# mach_nguyen_li_dttt1.net
KiCad netlist of a schematic drawn in Altium Designer
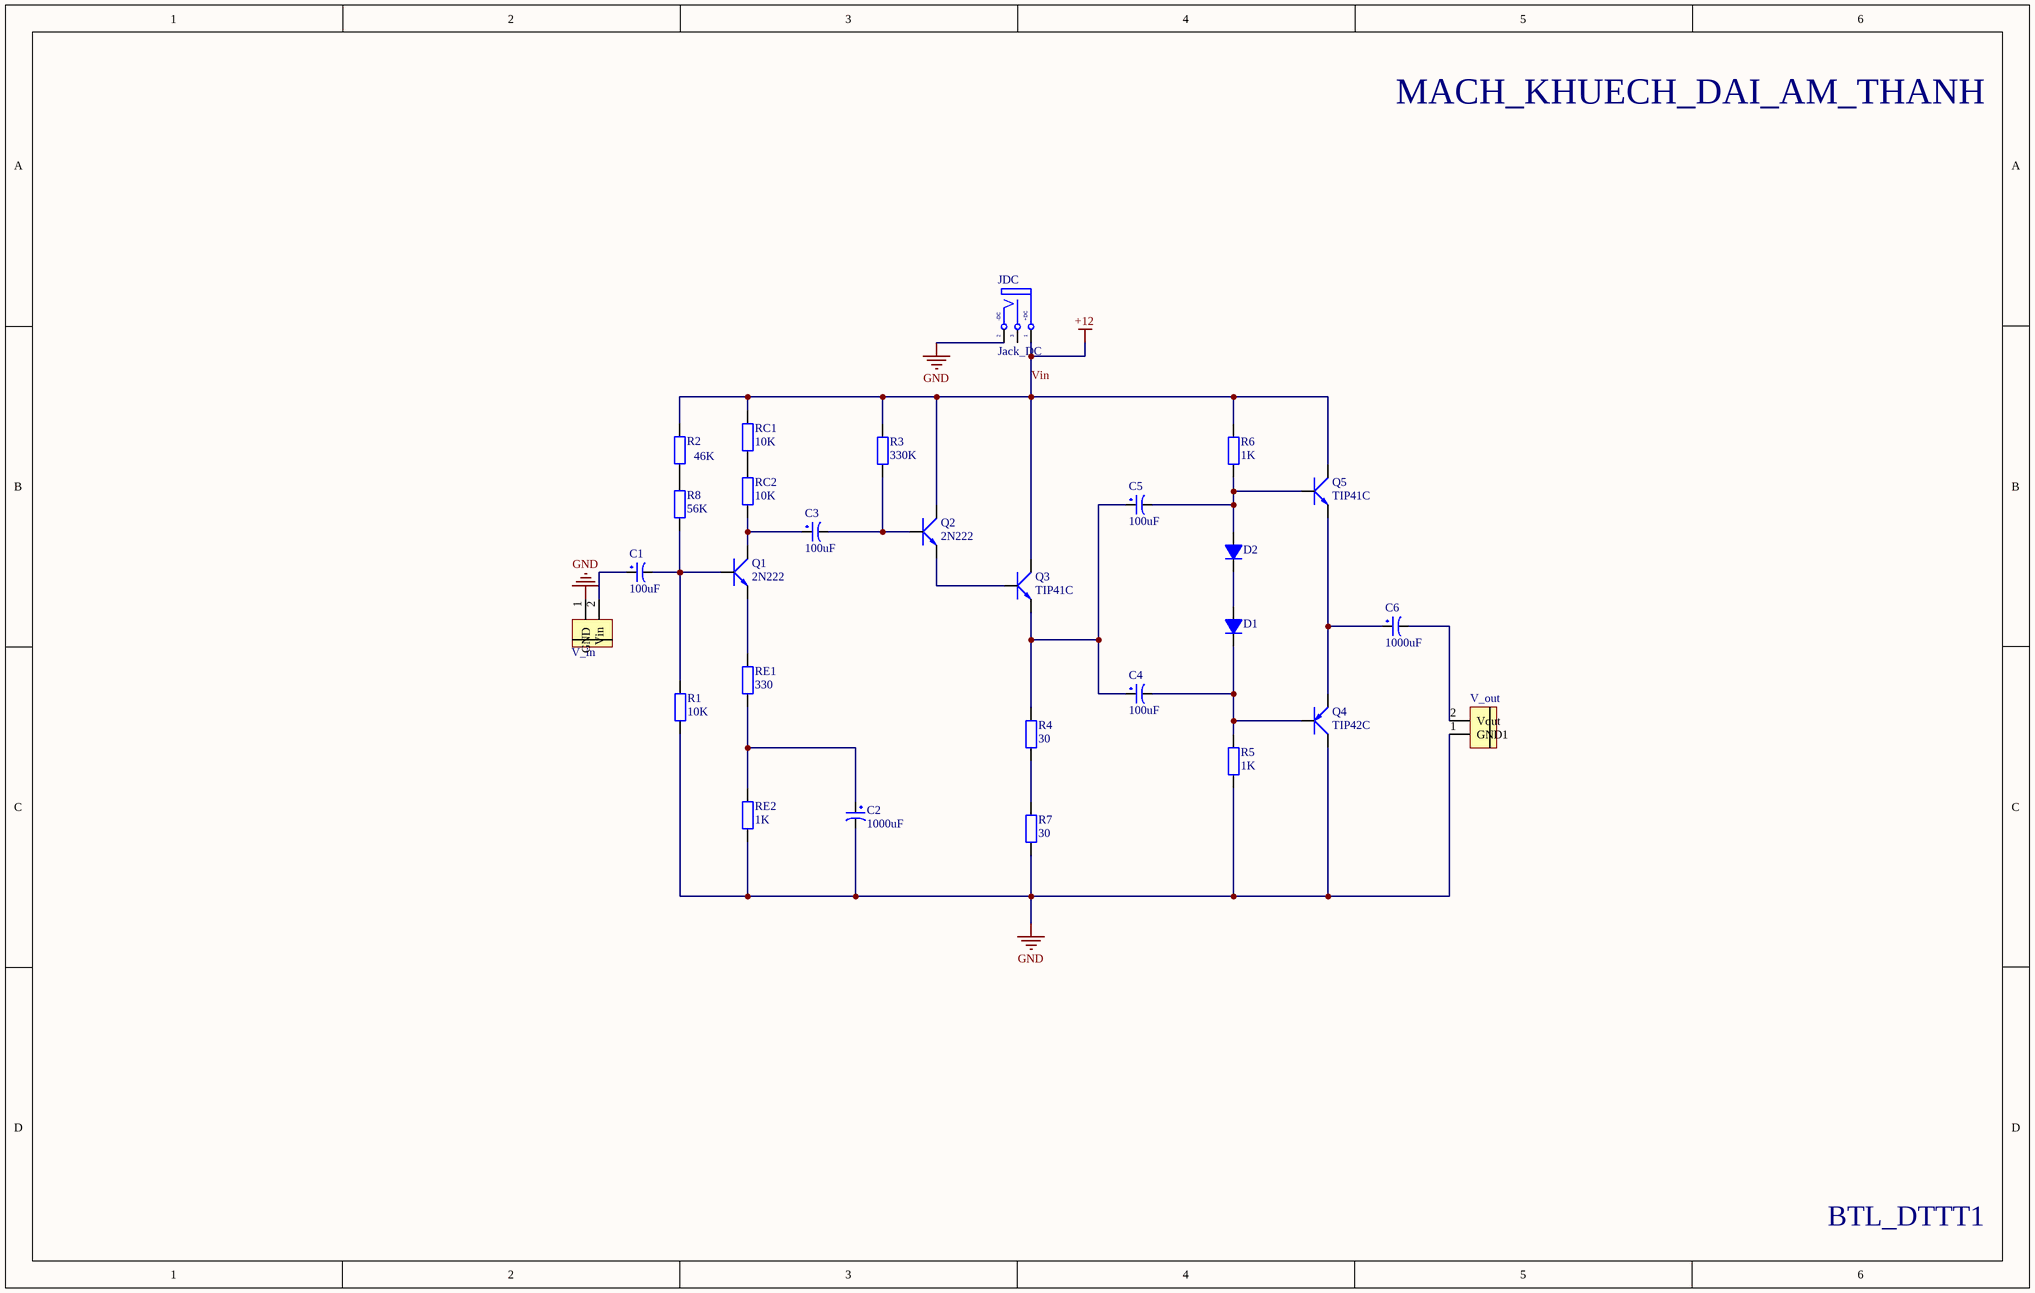
[diagram p0: mach_nguyen_li_dttt1.SchDoc]

(export (version "E")
  (design (tool "Eeschema 10.0.6"))
  (components
    (comp (ref "C1")
      (value "100uF")
      (footprint "tu hoa 5mm")
      (description "Cắm")
      (libsource (lib "Tu dien") (part "Tu Hoa 100uF 16V 5x11"))
    )
    (comp (ref "C2")
      (value "1000uF")
      (footprint "tu hoa 13mm")
      (description "Cắm")
      (libsource (lib "") (part "Tu Hoa 1000uF 25V 13x21_1"))
    )
    (comp (ref "C3")
      (value "100uF")
      (footprint "tu hoa 5mm")
      (description "Cắm")
      (libsource (lib "Tu dien") (part "Tu Hoa 100uF 16V 5x11"))
    )
    (comp (ref "C4")
      (value "100uF")
      (footprint "tu hoa 5mm")
      (description "Cắm")
      (libsource (lib "Tu dien") (part "Tu Hoa 100uF 16V 5x11"))
    )
    (comp (ref "C5")
      (value "100uF")
      (footprint "tu hoa 5mm")
      (description "Cắm")
      (libsource (lib "Tu dien") (part "Tu Hoa 100uF 16V 5x11"))
    )
    (comp (ref "C6")
      (value "1000uF")
      (footprint "tu hoa 13mm")
      (description "Cắm")
      (libsource (lib "Tu dien") (part "Tu Hoa 1000uF 25V 13x21"))
    )
    (comp (ref "D1")
      (value "100v")
      (footprint "DIODE 1A")
      (description "Cắm")
      (libsource (lib "Diode") (part "Diode 1N4007"))
    )
    (comp (ref "D2")
      (value "100v")
      (footprint "DIODE 1A")
      (description "Cắm")
      (libsource (lib "Diode") (part "Diode 1N4007"))
    )
    (comp (ref "JDC")
      (value "Jack_DC")
      (footprint "DC-IN_DC050-T")
      (description "Surface Mount，Right Angle DC Power Receptacle 2mm 6.4mm 4A 16V SMD AC/DC Power Connectors ROHS")
      (fields (field (name "PARTNUMBER") "DC050-T") (field (name "CREATOR") "Manhpd"))
      (libsource (lib "MKP_lib") (part "DCIN"))
    )
    (comp (ref "Q1")
      (value "2N222")
      (footprint "TO92-123")
      (description "NPN 600mW, ECB")
      (libsource (lib "Library") (part "2N222"))
    )
    (comp (ref "Q2")
      (value "2N222")
      (footprint "TO92-123")
      (description "NPN 600mW, ECB")
      (libsource (lib "Library") (part "2N222"))
    )
    (comp (ref "Q3")
      (value "TIP41C")
      (footprint "TO220-123")
      (description "NPN 2W, BCE")
      (libsource (lib "Library") (part "TIP41C"))
    )
    (comp (ref "Q4")
      (value "TIP42C")
      (footprint "TO220-123")
      (description "PNP 2W, BCE")
      (libsource (lib "Library") (part "TIP42C"))
    )
    (comp (ref "Q5")
      (value "TIP41C")
      (footprint "TO220-123")
      (description "NPN 2W, BCE")
      (libsource (lib "Library") (part "TIP41C"))
    )
    (comp (ref "R1")
      (value "10K")
      (footprint "tro vach 1/2w")
      (description "Cắm")
      (libsource (lib "Dien Tro") (part "Tro Vach 1/2W 5% 820R"))
    )
    (comp (ref "R2")
      (value "46K")
      (footprint "tro vach 1/2w")
      (description "Cắm")
      (libsource (lib "Dien Tro") (part "Tro Vach 1/2W 5% 820R"))
    )
    (comp (ref "R3")
      (value "330K")
      (footprint "tro vach 1/2w")
      (description "Cắm")
      (libsource (lib "Dien Tro") (part "Tro Vach 1/2W 5% 820R"))
    )
    (comp (ref "R4")
      (value "30")
      (footprint "tro vach 1/2w")
      (description "Cắm")
      (libsource (lib "Dien Tro") (part "Tro Vach 1/2W 5% 820R"))
    )
    (comp (ref "R5")
      (value "1K")
      (footprint "tro vach 1/2w")
      (description "Cắm")
      (libsource (lib "Dien Tro") (part "Tro Vach 1/2W 5% 820R"))
    )
    (comp (ref "R6")
      (value "1K")
      (footprint "tro vach 1/2w")
      (description "Cắm")
      (libsource (lib "Dien Tro") (part "Tro Vach 1/2W 5% 820R"))
    )
    (comp (ref "R7")
      (value "30")
      (footprint "tro vach 1/2w")
      (description "Cắm")
      (libsource (lib "Dien Tro") (part "Tro Vach 1/2W 5% 820R"))
    )
    (comp (ref "R8")
      (value "56K")
      (footprint "tro vach 1/2w")
      (description "Cắm")
      (libsource (lib "Dien Tro") (part "Tro Vach 1/2W 5% 820R"))
    )
    (comp (ref "RC1")
      (value "10K")
      (footprint "tro vach 1/2w")
      (description "Cắm")
      (libsource (lib "Dien Tro") (part "Tro Vach 1/2W 5% 820R"))
    )
    (comp (ref "RC2")
      (value "10K")
      (footprint "tro vach 1/2w")
      (description "Cắm")
      (libsource (lib "Dien Tro") (part "Tro Vach 1/2W 5% 820R"))
    )
    (comp (ref "RE1")
      (value "330")
      (footprint "tro vach 1/2w")
      (description "Cắm")
      (libsource (lib "Dien Tro") (part "Tro Vach 1/2W 5% 820R"))
    )
    (comp (ref "RE2")
      (value "1K")
      (footprint "tro vach 1/2w")
      (description "Cắm")
      (libsource (lib "Dien Tro") (part "Tro Vach 1/2W 5% 820R"))
    )
    (comp (ref "V_in")
      (value "CON 2 KF301")
      (footprint "Con 2 KF301 5.08")
      (description "Cắm")
      (libsource (lib "") (part "CON 2 KF301_1"))
    )
    (comp (ref "V_out")
      (value "CON 2 KF301")
      (footprint "Con 2 KF301 5.08")
      (description "Cắm")
      (libsource (lib "Connector") (part "CON 2 KF301"))
    )
  )
  (nets
    (net (code "1") (name "+12") (class "Default")
      (node (ref "JDC") (pin "1") (pinfunction "T_1") (pintype "passive"))
      (node (ref "Q2") (pin "3") (pinfunction "C_3") (pintype "passive"))
      (node (ref "Q3") (pin "2") (pinfunction "C_2") (pintype "passive"))
      (node (ref "Q5") (pin "2") (pinfunction "C_2") (pintype "passive"))
      (node (ref "R2") (pin "2") (pinfunction "2_2") (pintype "passive"))
      (node (ref "R3") (pin "2") (pinfunction "2_2") (pintype "passive"))
      (node (ref "R6") (pin "2") (pinfunction "2_2") (pintype "passive"))
      (node (ref "RC1") (pin "2") (pinfunction "2_2") (pintype "passive"))
    )
    (net (code "2") (name "GND") (class "Default")
      (node (ref "C2") (pin "2") (pinfunction "2_2") (pintype "passive"))
      (node (ref "JDC") (pin "2") (pinfunction "TN_2") (pintype "passive"))
      (node (ref "Q4") (pin "2") (pinfunction "C_2") (pintype "passive"))
      (node (ref "R1") (pin "1") (pinfunction "1_1") (pintype "passive"))
      (node (ref "R5") (pin "1") (pinfunction "1_1") (pintype "passive"))
      (node (ref "R7") (pin "1") (pinfunction "1_1") (pintype "passive"))
      (node (ref "RE2") (pin "1") (pinfunction "1_1") (pintype "passive"))
      (node (ref "V_in") (pin "1") (pinfunction "GND_1") (pintype "passive"))
      (node (ref "V_out") (pin "1") (pinfunction "GND1_1") (pintype "passive"))
    )
    (net (code "3") (name "Net-(C2-Pad1)") (class "Default")
      (node (ref "C2") (pin "1") (pinfunction "1_1") (pintype "passive"))
      (node (ref "RE1") (pin "1") (pinfunction "1_1") (pintype "passive"))
      (node (ref "RE2") (pin "2") (pinfunction "2_2") (pintype "passive"))
    )
    (net (code "4") (name "Net-(D1-A)") (class "Default")
      (node (ref "D1") (pin "1") (pinfunction "A_1") (pintype "passive"))
      (node (ref "D2") (pin "2") (pinfunction "K_2") (pintype "passive"))
    )
    (net (code "5") (name "Net-(D1-K)") (class "Default")
      (node (ref "C4") (pin "2") (pinfunction "2_2") (pintype "passive"))
      (node (ref "D1") (pin "2") (pinfunction "K_2") (pintype "passive"))
      (node (ref "Q4") (pin "1") (pinfunction "B_1") (pintype "passive"))
      (node (ref "R5") (pin "2") (pinfunction "2_2") (pintype "passive"))
    )
    (net (code "6") (name "Net-(D2-A)") (class "Default")
      (node (ref "C5") (pin "2") (pinfunction "2_2") (pintype "passive"))
      (node (ref "D2") (pin "1") (pinfunction "A_1") (pintype "passive"))
      (node (ref "Q5") (pin "1") (pinfunction "B_1") (pintype "passive"))
      (node (ref "R6") (pin "1") (pinfunction "1_1") (pintype "passive"))
    )
    (net (code "7") (name "Net-(Q1-B)") (class "Default")
      (node (ref "C1") (pin "2") (pinfunction "2_2") (pintype "passive"))
      (node (ref "Q1") (pin "2") (pinfunction "B_2") (pintype "passive"))
      (node (ref "R1") (pin "2") (pinfunction "2_2") (pintype "passive"))
      (node (ref "R8") (pin "1") (pinfunction "1_1") (pintype "passive"))
    )
    (net (code "8") (name "Net-(Q1-C)") (class "Default")
      (node (ref "C3") (pin "1") (pinfunction "1_1") (pintype "passive"))
      (node (ref "Q1") (pin "3") (pinfunction "C_3") (pintype "passive"))
      (node (ref "RC2") (pin "1") (pinfunction "1_1") (pintype "passive"))
    )
    (net (code "9") (name "Net-(Q1-E)") (class "Default")
      (node (ref "Q1") (pin "1") (pinfunction "E_1") (pintype "passive"))
      (node (ref "RE1") (pin "2") (pinfunction "2_2") (pintype "passive"))
    )
    (net (code "10") (name "Net-(Q2-B)") (class "Default")
      (node (ref "C3") (pin "2") (pinfunction "2_2") (pintype "passive"))
      (node (ref "Q2") (pin "2") (pinfunction "B_2") (pintype "passive"))
      (node (ref "R3") (pin "1") (pinfunction "1_1") (pintype "passive"))
    )
    (net (code "11") (name "Net-(Q2-E)") (class "Default")
      (node (ref "Q2") (pin "1") (pinfunction "E_1") (pintype "passive"))
      (node (ref "Q3") (pin "1") (pinfunction "B_1") (pintype "passive"))
    )
    (net (code "12") (name "Net-(Q3-E)") (class "Default")
      (node (ref "C4") (pin "1") (pinfunction "1_1") (pintype "passive"))
      (node (ref "C5") (pin "1") (pinfunction "1_1") (pintype "passive"))
      (node (ref "Q3") (pin "3") (pinfunction "E_3") (pintype "passive"))
      (node (ref "R4") (pin "2") (pinfunction "2_2") (pintype "passive"))
    )
    (net (code "13") (name "Net-(Q4-E)") (class "Default")
      (node (ref "C6") (pin "1") (pinfunction "1_1") (pintype "passive"))
      (node (ref "Q4") (pin "3") (pinfunction "E_3") (pintype "passive"))
      (node (ref "Q5") (pin "3") (pinfunction "E_3") (pintype "passive"))
    )
    (net (code "14") (name "Net-(R2-Pad1)") (class "Default")
      (node (ref "R2") (pin "1") (pinfunction "1_1") (pintype "passive"))
      (node (ref "R8") (pin "2") (pinfunction "2_2") (pintype "passive"))
    )
    (net (code "15") (name "Net-(R4-Pad1)") (class "Default")
      (node (ref "R4") (pin "1") (pinfunction "1_1") (pintype "passive"))
      (node (ref "R7") (pin "2") (pinfunction "2_2") (pintype "passive"))
    )
    (net (code "16") (name "Net-(RC1-Pad1)") (class "Default")
      (node (ref "RC1") (pin "1") (pinfunction "1_1") (pintype "passive"))
      (node (ref "RC2") (pin "2") (pinfunction "2_2") (pintype "passive"))
    )
    (net (code "17") (name "Net-(V_in-Vin)") (class "Default")
      (node (ref "C1") (pin "1") (pinfunction "1_1") (pintype "passive"))
      (node (ref "V_in") (pin "2") (pinfunction "Vin_2") (pintype "passive"))
    )
    (net (code "18") (name "Net-(V_out-Vout)") (class "Default")
      (node (ref "C6") (pin "2") (pinfunction "2_2") (pintype "passive"))
      (node (ref "V_out") (pin "2") (pinfunction "Vout_2") (pintype "passive"))
    )
    (net (code "19") (name "unconnected-(JDC-S-Pad3)") (class "Default")
      (node (ref "JDC") (pin "3") (pinfunction "S_3") (pintype "power_in"))
    )
  )
)
